# SCH.net
KiCad netlist of a schematic drawn in Altium Designer
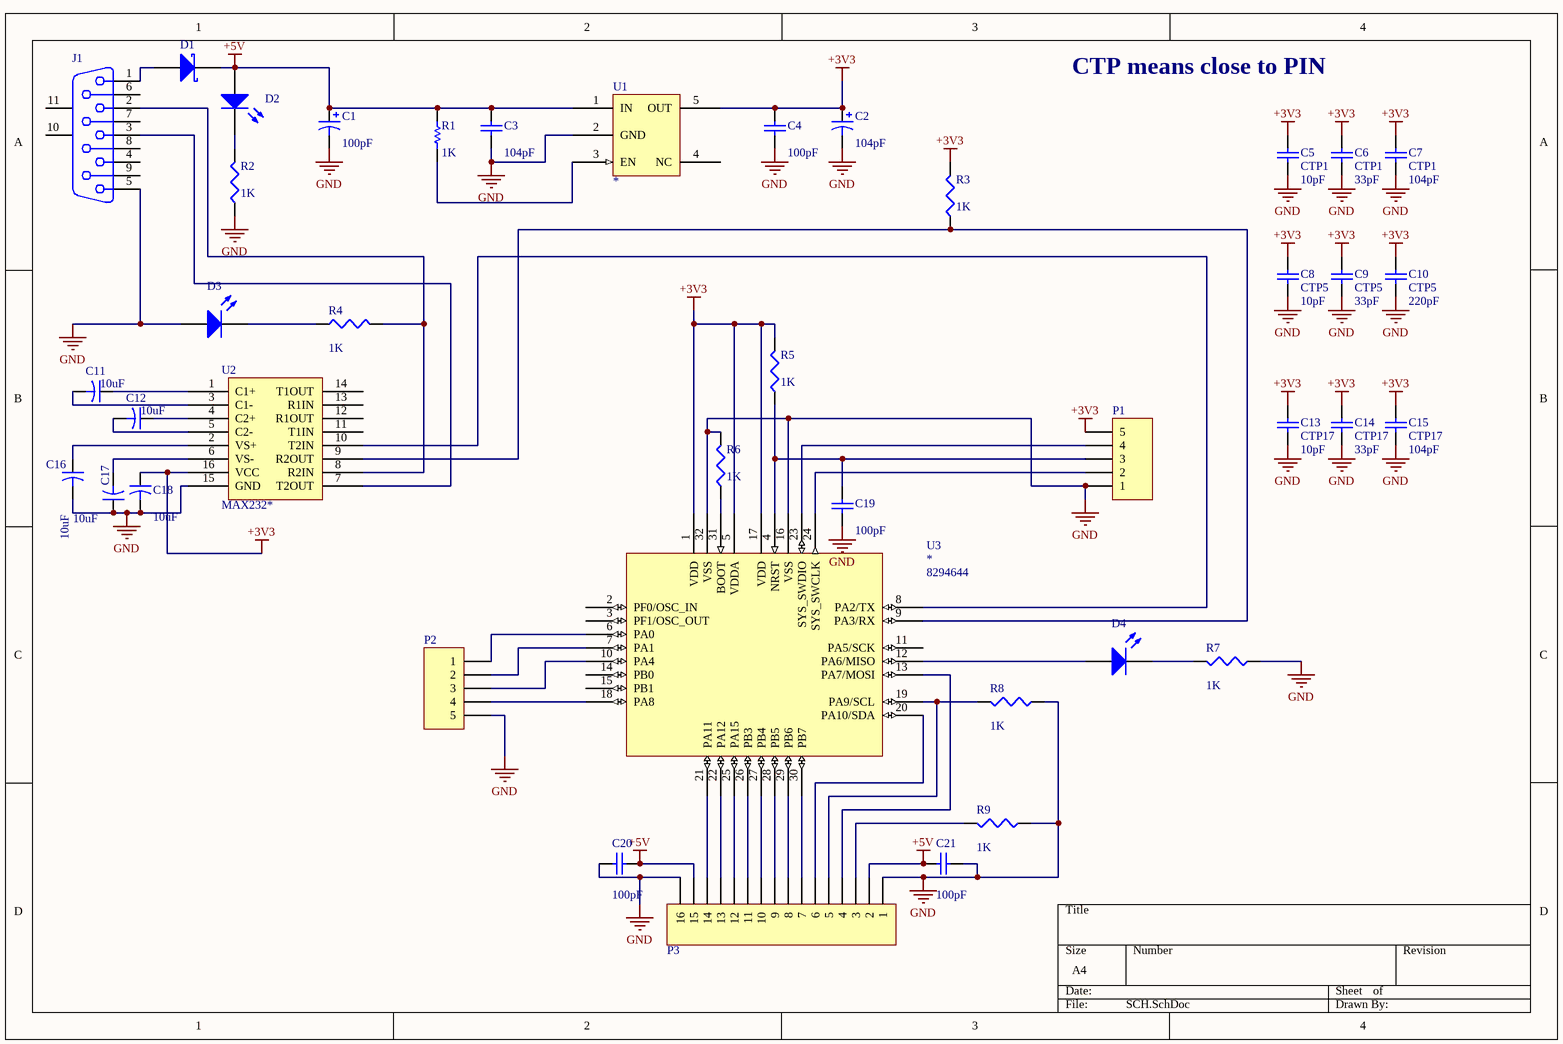
[diagram p0: SCH.SchDoc]

(export (version "E")
  (design (tool "Eeschema 10.0.6"))
  (components
    (comp (ref "C1")
      (value "100pF")
      (footprint "RB7.6-15")
      (description "Polarized Capacitor (Radial)")
      (fields (field (name "PUBLISHER") "Altium Limited"))
      (libsource (lib "Miscellaneous Devices") (part "Cap Pol1"))
    )
    (comp (ref "C2")
      (value "104pF")
      (footprint "RB7.6-15")
      (description "Polarized Capacitor (Radial)")
      (fields (field (name "PUBLISHER") "Altium Limited"))
      (libsource (lib "Miscellaneous Devices") (part "Cap Pol1"))
    )
    (comp (ref "C3")
      (value "104pF")
      (footprint "0603")
      (description "Capacitor")
      (fields (field (name "PUBLISHER") "Altium Limited"))
      (libsource (lib "Miscellaneous Devices") (part "Cap"))
    )
    (comp (ref "C4")
      (value "100pF")
      (footprint "0603")
      (description "Capacitor")
      (fields (field (name "PUBLISHER") "Altium Limited"))
      (libsource (lib "Miscellaneous Devices") (part "Cap"))
    )
    (comp (ref "C5")
      (value "CTP1")
      (footprint "0603")
      (description "Capacitor")
      (fields (field (name "ALTIUM_VALUE") "10pF") (field (name "PUBLISHER") "Altium Limited"))
      (libsource (lib "Miscellaneous Devices") (part "Cap"))
    )
    (comp (ref "C6")
      (value "CTP1")
      (footprint "0603")
      (description "Capacitor")
      (fields (field (name "ALTIUM_VALUE") "33pF") (field (name "PUBLISHER") "Altium Limited"))
      (libsource (lib "Miscellaneous Devices") (part "Cap"))
    )
    (comp (ref "C7")
      (value "CTP1")
      (footprint "0603")
      (description "Capacitor")
      (fields (field (name "ALTIUM_VALUE") "104pF") (field (name "PUBLISHER") "Altium Limited"))
      (libsource (lib "Miscellaneous Devices") (part "Cap"))
    )
    (comp (ref "C8")
      (value "CTP5")
      (footprint "0603")
      (description "Capacitor")
      (fields (field (name "ALTIUM_VALUE") "10pF") (field (name "PUBLISHER") "Altium Limited"))
      (libsource (lib "Miscellaneous Devices") (part "Cap"))
    )
    (comp (ref "C9")
      (value "CTP5")
      (footprint "0603")
      (description "Capacitor")
      (fields (field (name "ALTIUM_VALUE") "33pF") (field (name "PUBLISHER") "Altium Limited"))
      (libsource (lib "Miscellaneous Devices") (part "Cap"))
    )
    (comp (ref "C10")
      (value "CTP5")
      (footprint "0603")
      (description "Capacitor")
      (fields (field (name "ALTIUM_VALUE") "220pF") (field (name "PUBLISHER") "Altium Limited"))
      (libsource (lib "Miscellaneous Devices") (part "Cap"))
    )
    (comp (ref "C11")
      (value "10uF")
      (footprint "CAPR5-4X5")
      (description "Capacitor")
      (fields (field (name "PUBLISHER") "Altium Limited"))
      (libsource (lib "Miscellaneous Devices") (part "Cap2"))
    )
    (comp (ref "C12")
      (value "10uF")
      (footprint "CAPR5-4X5")
      (description "Capacitor")
      (fields (field (name "PUBLISHER") "Altium Limited"))
      (libsource (lib "Miscellaneous Devices") (part "Cap2"))
    )
    (comp (ref "C13")
      (value "CTP17")
      (footprint "0603")
      (description "Capacitor")
      (fields (field (name "ALTIUM_VALUE") "10pF") (field (name "PUBLISHER") "Altium Limited"))
      (libsource (lib "Miscellaneous Devices") (part "Cap"))
    )
    (comp (ref "C14")
      (value "CTP17")
      (footprint "0603")
      (description "Capacitor")
      (fields (field (name "ALTIUM_VALUE") "33pF") (field (name "PUBLISHER") "Altium Limited"))
      (libsource (lib "Miscellaneous Devices") (part "Cap"))
    )
    (comp (ref "C15")
      (value "CTP17")
      (footprint "0603")
      (description "Capacitor")
      (fields (field (name "ALTIUM_VALUE") "104pF") (field (name "PUBLISHER") "Altium Limited"))
      (libsource (lib "Miscellaneous Devices") (part "Cap"))
    )
    (comp (ref "C16")
      (value "10uF")
      (footprint "CAPR5-4X5")
      (description "Capacitor")
      (fields (field (name "PUBLISHER") "Altium Limited"))
      (libsource (lib "Miscellaneous Devices") (part "Cap2"))
    )
    (comp (ref "C17")
      (value "10uF")
      (footprint "CAPR5-4X5")
      (description "Capacitor")
      (fields (field (name "PUBLISHER") "Altium Limited"))
      (libsource (lib "Miscellaneous Devices") (part "Cap2"))
    )
    (comp (ref "C18")
      (value "10uF")
      (footprint "CAPR5-4X5")
      (description "Capacitor")
      (fields (field (name "PUBLISHER") "Altium Limited"))
      (libsource (lib "Miscellaneous Devices") (part "Cap2"))
    )
    (comp (ref "C19")
      (value "100pF")
      (footprint "0603")
      (description "Capacitor")
      (fields (field (name "PUBLISHER") "Altium Limited"))
      (libsource (lib "Miscellaneous Devices") (part "Cap"))
    )
    (comp (ref "C20")
      (value "100pF")
      (footprint "0603")
      (description "Capacitor")
      (fields (field (name "PUBLISHER") "Altium Limited"))
      (libsource (lib "Miscellaneous Devices") (part "Cap"))
    )
    (comp (ref "C21")
      (value "100pF")
      (footprint "0603")
      (description "Capacitor")
      (fields (field (name "PUBLISHER") "Altium Limited"))
      (libsource (lib "Miscellaneous Devices") (part "Cap"))
    )
    (comp (ref "D1")
      (value "~")
      (footprint "SMB")
      (description "Schottky Diode")
      (fields (field (name "PUBLISHER") "Altium Limited"))
      (libsource (lib "Miscellaneous Devices") (part "D Schottky"))
    )
    (comp (ref "D2")
      (value "~")
      (footprint "0805D")
      (description "Typical INFRARED GaAs LED")
      (fields (field (name "PUBLISHER") "Altium Limited"))
      (libsource (lib "Miscellaneous Devices") (part "LED0"))
    )
    (comp (ref "D3")
      (value "~")
      (footprint "0805D")
      (description "Typical INFRARED GaAs LED")
      (fields (field (name "PUBLISHER") "Altium Limited"))
      (libsource (lib "Miscellaneous Devices") (part "LED0"))
    )
    (comp (ref "D4")
      (value "~")
      (footprint "0805D")
      (description "Typical INFRARED GaAs LED")
      (fields (field (name "PUBLISHER") "Altium Limited"))
      (libsource (lib "Miscellaneous Devices") (part "LED0"))
    )
    (comp (ref "J1")
      (value "~")
      (footprint "DSUB1.385-2H9")
      (description "Receptacle Assembly, 9 Position, Right Angle")
      (fields (field (name "PUBLISHER") "Altium Limited"))
      (libsource (lib "Miscellaneous Connectors") (part "D Connector 9"))
    )
    (comp (ref "P1")
      (value "~")
      (footprint "HDR1X5")
      (description "Header, 5-Pin")
      (fields (field (name "PUBLISHER") "Altium Limited"))
      (libsource (lib "") (part "Header 5_1"))
    )
    (comp (ref "P2")
      (value "~")
      (footprint "HDR1X5")
      (description "Header, 5-Pin")
      (fields (field (name "PUBLISHER") "Altium Limited"))
      (libsource (lib "Miscellaneous Connectors") (part "Header 5"))
    )
    (comp (ref "P3")
      (value "~")
      (footprint "HDR1X16")
      (description "Header, 16-Pin")
      (fields (field (name "PUBLISHER") "Altium Limited"))
      (libsource (lib "Miscellaneous Connectors") (part "Header 16"))
    )
    (comp (ref "R1")
      (value "1K")
      (footprint "0603")
      (description "Semiconductor Resistor")
      (fields (field (name "PUBLISHER") "Altium Limited"))
      (libsource (lib "Miscellaneous Devices") (part "Res Semi"))
    )
    (comp (ref "R2")
      (value "1K")
      (footprint "0603")
      (description "Resistor")
      (fields (field (name "PUBLISHER") "Altium Limited"))
      (libsource (lib "Miscellaneous Devices") (part "Res3"))
    )
    (comp (ref "R3")
      (value "1K")
      (footprint "0603")
      (description "Resistor")
      (fields (field (name "PUBLISHER") "Altium Limited"))
      (libsource (lib "Miscellaneous Devices") (part "Res3"))
    )
    (comp (ref "R4")
      (value "1K")
      (footprint "0603")
      (description "Resistor")
      (fields (field (name "PUBLISHER") "Altium Limited"))
      (libsource (lib "Miscellaneous Devices") (part "Res3"))
    )
    (comp (ref "R5")
      (value "1K")
      (footprint "0603")
      (description "Resistor")
      (fields (field (name "PUBLISHER") "Altium Limited"))
      (libsource (lib "Miscellaneous Devices") (part "Res3"))
    )
    (comp (ref "R6")
      (value "1K")
      (footprint "0603")
      (description "Resistor")
      (fields (field (name "PUBLISHER") "Altium Limited"))
      (libsource (lib "") (part "Res3_1"))
    )
    (comp (ref "R7")
      (value "1K")
      (footprint "0603")
      (description "Resistor")
      (fields (field (name "PUBLISHER") "Altium Limited"))
      (libsource (lib "") (part "Res3_1"))
    )
    (comp (ref "R8")
      (value "1K")
      (footprint "0603")
      (description "Resistor")
      (fields (field (name "PUBLISHER") "Altium Limited"))
      (libsource (lib "") (part "Res3_1"))
    )
    (comp (ref "R9")
      (value "1K")
      (footprint "0603")
      (description "Resistor")
      (fields (field (name "PUBLISHER") "Altium Limited"))
      (libsource (lib "") (part "Res3_1"))
    )
    (comp (ref "U1") (value "*") (footprint "SOT-23-5L") (libsource (lib "MyAltiumSchlib1") (part "VRH3302")))
    (comp (ref "U2")
      (value "MAX232*")
      (footprint "SSOP16")
      (libsource (lib "MyAltiumSchlib1") (part "MAX232"))
    )
    (comp (ref "U3")
      (value "*")
      (footprint "LQFP32")
      (fields (field (name "SUPPLIER PART NUMBER 1") "8294644"))
      (libsource (lib "MyAltiumSchlib1") (part "STM32F030K6"))
    )
  )
  (nets
    (net (code "1") (name "+3V3") (class "Default")
      (node (ref "C10") (pin "2") (pinfunction "2_2") (pintype "passive"))
      (node (ref "C13") (pin "2") (pinfunction "2_2") (pintype "passive"))
      (node (ref "C14") (pin "2") (pinfunction "2_2") (pintype "passive"))
      (node (ref "C15") (pin "2") (pinfunction "2_2") (pintype "passive"))
      (node (ref "C18") (pin "1") (pinfunction "1_1") (pintype "passive"))
      (node (ref "C2") (pin "1") (pinfunction "1_1") (pintype "passive"))
      (node (ref "C4") (pin "2") (pinfunction "2_2") (pintype "passive"))
      (node (ref "C5") (pin "2") (pinfunction "2_2") (pintype "passive"))
      (node (ref "C6") (pin "2") (pinfunction "2_2") (pintype "passive"))
      (node (ref "C7") (pin "2") (pinfunction "2_2") (pintype "passive"))
      (node (ref "C8") (pin "2") (pinfunction "2_2") (pintype "passive"))
      (node (ref "C9") (pin "2") (pinfunction "2_2") (pintype "passive"))
      (node (ref "P1") (pin "5") (pinfunction "5_5") (pintype "passive"))
      (node (ref "R3") (pin "2") (pinfunction "2_2") (pintype "passive"))
      (node (ref "R5") (pin "2") (pinfunction "2_2") (pintype "passive"))
      (node (ref "U1") (pin "5") (pinfunction "OUT_5") (pintype "power_in"))
      (node (ref "U2") (pin "16") (pinfunction "VCC_16") (pintype "passive"))
      (node (ref "U3") (pin "1") (pinfunction "VDD_1") (pintype "power_in"))
      (node (ref "U3") (pin "17") (pinfunction "VDD_17") (pintype "power_in"))
      (node (ref "U3") (pin "5") (pinfunction "VDDA_5") (pintype "power_in"))
    )
    (net (code "2") (name "+5V") (class "Default")
      (node (ref "C1") (pin "1") (pinfunction "1_1") (pintype "passive"))
      (node (ref "C20") (pin "1") (pinfunction "1_1") (pintype "passive"))
      (node (ref "C21") (pin "2") (pinfunction "2_2") (pintype "passive"))
      (node (ref "C3") (pin "2") (pinfunction "2_2") (pintype "passive"))
      (node (ref "D1") (pin "2") (pinfunction "K_2") (pintype "passive"))
      (node (ref "D2") (pin "1") (pinfunction "A_1") (pintype "passive"))
      (node (ref "P3") (pin "15") (pinfunction "15_15") (pintype "passive"))
      (node (ref "P3") (pin "2") (pinfunction "2_2") (pintype "passive"))
      (node (ref "R1") (pin "2") (pinfunction "2_2") (pintype "passive"))
      (node (ref "U1") (pin "1") (pinfunction "IN_1") (pintype "power_in"))
    )
    (net (code "3") (name "GND") (class "Default")
      (node (ref "C1") (pin "2") (pinfunction "2_2") (pintype "passive"))
      (node (ref "C10") (pin "1") (pinfunction "1_1") (pintype "passive"))
      (node (ref "C13") (pin "1") (pinfunction "1_1") (pintype "passive"))
      (node (ref "C14") (pin "1") (pinfunction "1_1") (pintype "passive"))
      (node (ref "C15") (pin "1") (pinfunction "1_1") (pintype "passive"))
      (node (ref "C16") (pin "2") (pinfunction "2_2") (pintype "passive"))
      (node (ref "C17") (pin "1") (pinfunction "1_1") (pintype "passive"))
      (node (ref "C18") (pin "2") (pinfunction "2_2") (pintype "passive"))
      (node (ref "C19") (pin "1") (pinfunction "1_1") (pintype "passive"))
      (node (ref "C2") (pin "2") (pinfunction "2_2") (pintype "passive"))
      (node (ref "C20") (pin "2") (pinfunction "2_2") (pintype "passive"))
      (node (ref "C21") (pin "1") (pinfunction "1_1") (pintype "passive"))
      (node (ref "C3") (pin "1") (pinfunction "1_1") (pintype "passive"))
      (node (ref "C4") (pin "1") (pinfunction "1_1") (pintype "passive"))
      (node (ref "C5") (pin "1") (pinfunction "1_1") (pintype "passive"))
      (node (ref "C6") (pin "1") (pinfunction "1_1") (pintype "passive"))
      (node (ref "C7") (pin "1") (pinfunction "1_1") (pintype "passive"))
      (node (ref "C8") (pin "1") (pinfunction "1_1") (pintype "passive"))
      (node (ref "C9") (pin "1") (pinfunction "1_1") (pintype "passive"))
      (node (ref "D3") (pin "1") (pinfunction "A_1") (pintype "passive"))
      (node (ref "J1") (pin "5") (pinfunction "5_5") (pintype "passive"))
      (node (ref "P1") (pin "1") (pinfunction "1_1") (pintype "passive"))
      (node (ref "P2") (pin "5") (pinfunction "5_5") (pintype "passive"))
      (node (ref "P3") (pin "1") (pinfunction "1_1") (pintype "passive"))
      (node (ref "P3") (pin "16") (pinfunction "16_16") (pintype "passive"))
      (node (ref "R2") (pin "1") (pinfunction "1_1") (pintype "passive"))
      (node (ref "R6") (pin "1") (pinfunction "1_1") (pintype "passive"))
      (node (ref "R7") (pin "2") (pinfunction "2_2") (pintype "passive"))
      (node (ref "R8") (pin "2") (pinfunction "2_2") (pintype "passive"))
      (node (ref "R9") (pin "2") (pinfunction "2_2") (pintype "passive"))
      (node (ref "U1") (pin "2") (pinfunction "GND_2") (pintype "power_in"))
      (node (ref "U2") (pin "15") (pinfunction "GND_15") (pintype "passive"))
      (node (ref "U3") (pin "16") (pinfunction "VSS_16") (pintype "power_in"))
      (node (ref "U3") (pin "32") (pinfunction "VSS_32") (pintype "power_in"))
    )
    (net (code "4") (name "Net-(D1-A)") (class "Default")
      (node (ref "D1") (pin "1") (pinfunction "A_1") (pintype "passive"))
      (node (ref "J1") (pin "1") (pinfunction "1_1") (pintype "passive"))
    )
    (net (code "5") (name "Net-(D2-K)") (class "Default")
      (node (ref "D2") (pin "2") (pinfunction "K_2") (pintype "passive"))
      (node (ref "R2") (pin "2") (pinfunction "2_2") (pintype "passive"))
    )
    (net (code "6") (name "Net-(D3-K)") (class "Default")
      (node (ref "D3") (pin "2") (pinfunction "K_2") (pintype "passive"))
      (node (ref "R4") (pin "1") (pinfunction "1_1") (pintype "passive"))
    )
    (net (code "7") (name "Net-(D4-A)") (class "Default")
      (node (ref "D4") (pin "1") (pinfunction "A_1") (pintype "passive"))
      (node (ref "U3") (pin "12") (pinfunction "PA6/MISO_12") (pintype "bidirectional"))
    )
    (net (code "8") (name "Net-(D4-K)") (class "Default")
      (node (ref "D4") (pin "2") (pinfunction "K_2") (pintype "passive"))
      (node (ref "R7") (pin "1") (pinfunction "1_1") (pintype "passive"))
    )
    (net (code "9") (name "Net-(P3-Pad3)") (class "Default")
      (node (ref "P3") (pin "3") (pinfunction "3_3") (pintype "passive"))
      (node (ref "R9") (pin "1") (pinfunction "1_1") (pintype "passive"))
    )
    (net (code "10") (name "Net-(U1-EN)") (class "Default")
      (node (ref "R1") (pin "1") (pinfunction "1_1") (pintype "passive"))
      (node (ref "U1") (pin "3") (pinfunction "EN_3") (pintype "input"))
    )
    (net (code "11") (name "Net-(U2-C1+)") (class "Default")
      (node (ref "C11") (pin "1") (pinfunction "1_1") (pintype "passive"))
      (node (ref "U2") (pin "1") (pinfunction "C1+_1") (pintype "passive"))
    )
    (net (code "12") (name "Net-(U2-C1-)") (class "Default")
      (node (ref "C11") (pin "2") (pinfunction "2_2") (pintype "passive"))
      (node (ref "U2") (pin "3") (pinfunction "C1-_3") (pintype "passive"))
    )
    (net (code "13") (name "Net-(U2-C2+)") (class "Default")
      (node (ref "C12") (pin "1") (pinfunction "1_1") (pintype "passive"))
      (node (ref "U2") (pin "4") (pinfunction "C2+_4") (pintype "passive"))
    )
    (net (code "14") (name "Net-(U2-C2-)") (class "Default")
      (node (ref "C12") (pin "2") (pinfunction "2_2") (pintype "passive"))
      (node (ref "U2") (pin "5") (pinfunction "C2-_5") (pintype "passive"))
    )
    (net (code "15") (name "Net-(U2-R2IN)") (class "Default")
      (node (ref "J1") (pin "2") (pinfunction "2_2") (pintype "passive"))
      (node (ref "R4") (pin "2") (pinfunction "2_2") (pintype "passive"))
      (node (ref "U2") (pin "8") (pinfunction "R2IN_8") (pintype "passive"))
    )
    (net (code "16") (name "Net-(U2-R2OUT)") (class "Default")
      (node (ref "R3") (pin "1") (pinfunction "1_1") (pintype "passive"))
      (node (ref "U2") (pin "9") (pinfunction "R2OUT_9") (pintype "passive"))
      (node (ref "U3") (pin "9") (pinfunction "PA3/RX_9") (pintype "bidirectional"))
    )
    (net (code "17") (name "Net-(U2-T2IN)") (class "Default")
      (node (ref "U2") (pin "10") (pinfunction "T2IN_10") (pintype "passive"))
      (node (ref "U3") (pin "8") (pinfunction "PA2/TX_8") (pintype "bidirectional"))
    )
    (net (code "18") (name "Net-(U2-T2OUT)") (class "Default")
      (node (ref "J1") (pin "3") (pinfunction "3_3") (pintype "passive"))
      (node (ref "U2") (pin "7") (pinfunction "T2OUT_7") (pintype "passive"))
    )
    (net (code "19") (name "Net-(U2-VS+)") (class "Default")
      (node (ref "C16") (pin "1") (pinfunction "1_1") (pintype "passive"))
      (node (ref "U2") (pin "2") (pinfunction "VS+_2") (pintype "passive"))
    )
    (net (code "20") (name "Net-(U2-VS-)") (class "Default")
      (node (ref "C17") (pin "2") (pinfunction "2_2") (pintype "passive"))
      (node (ref "U2") (pin "6") (pinfunction "VS-_6") (pintype "passive"))
    )
    (net (code "21") (name "Net-(U3-BOOT)") (class "Default")
      (node (ref "R6") (pin "2") (pinfunction "2_2") (pintype "passive"))
      (node (ref "U3") (pin "31") (pinfunction "BOOT_31") (pintype "input"))
    )
    (net (code "22") (name "Net-(U3-NRST)") (class "Default")
      (node (ref "C19") (pin "2") (pinfunction "2_2") (pintype "passive"))
      (node (ref "P1") (pin "3") (pinfunction "3_3") (pintype "passive"))
      (node (ref "R5") (pin "1") (pinfunction "1_1") (pintype "passive"))
      (node (ref "U3") (pin "4") (pinfunction "NRST_4") (pintype "input"))
    )
    (net (code "23") (name "Net-(U3-PA0)") (class "Default")
      (node (ref "P2") (pin "1") (pinfunction "1_1") (pintype "passive"))
      (node (ref "U3") (pin "6") (pinfunction "PA0_6") (pintype "bidirectional"))
    )
    (net (code "24") (name "Net-(U3-PA1)") (class "Default")
      (node (ref "P2") (pin "2") (pinfunction "2_2") (pintype "passive"))
      (node (ref "U3") (pin "7") (pinfunction "PA1_7") (pintype "bidirectional"))
    )
    (net (code "25") (name "Net-(U3-PA4)") (class "Default")
      (node (ref "P2") (pin "3") (pinfunction "3_3") (pintype "passive"))
      (node (ref "U3") (pin "10") (pinfunction "PA4_10") (pintype "bidirectional"))
    )
    (net (code "26") (name "Net-(U3-PA7{slash}MOSI)") (class "Default")
      (node (ref "P3") (pin "4") (pinfunction "4_4") (pintype "passive"))
      (node (ref "U3") (pin "13") (pinfunction "PA7/MOSI_13") (pintype "bidirectional"))
    )
    (net (code "27") (name "Net-(U3-PA8)") (class "Default")
      (node (ref "P2") (pin "4") (pinfunction "4_4") (pintype "passive"))
      (node (ref "U3") (pin "18") (pinfunction "PA8_18") (pintype "bidirectional"))
    )
    (net (code "28") (name "Net-(U3-PA9{slash}SCL)") (class "Default")
      (node (ref "P3") (pin "5") (pinfunction "5_5") (pintype "passive"))
      (node (ref "R8") (pin "1") (pinfunction "1_1") (pintype "passive"))
      (node (ref "U3") (pin "19") (pinfunction "PA9/SCL_19") (pintype "bidirectional"))
    )
    (net (code "29") (name "Net-(U3-PA10{slash}SDA)") (class "Default")
      (node (ref "P3") (pin "6") (pinfunction "6_6") (pintype "passive"))
      (node (ref "U3") (pin "20") (pinfunction "PA10/SDA_20") (pintype "bidirectional"))
    )
    (net (code "30") (name "Net-(U3-PA11)") (class "Default")
      (node (ref "P3") (pin "14") (pinfunction "14_14") (pintype "passive"))
      (node (ref "U3") (pin "21") (pinfunction "PA11_21") (pintype "bidirectional"))
    )
    (net (code "31") (name "Net-(U3-PA12)") (class "Default")
      (node (ref "P3") (pin "13") (pinfunction "13_13") (pintype "passive"))
      (node (ref "U3") (pin "22") (pinfunction "PA12_22") (pintype "bidirectional"))
    )
    (net (code "32") (name "Net-(U3-PA15)") (class "Default")
      (node (ref "P3") (pin "12") (pinfunction "12_12") (pintype "passive"))
      (node (ref "U3") (pin "25") (pinfunction "PA15_25") (pintype "bidirectional"))
    )
    (net (code "33") (name "Net-(U3-PB3)") (class "Default")
      (node (ref "P3") (pin "11") (pinfunction "11_11") (pintype "passive"))
      (node (ref "U3") (pin "26") (pinfunction "PB3_26") (pintype "bidirectional"))
    )
    (net (code "34") (name "Net-(U3-PB4)") (class "Default")
      (node (ref "P3") (pin "10") (pinfunction "10_10") (pintype "passive"))
      (node (ref "U3") (pin "27") (pinfunction "PB4_27") (pintype "bidirectional"))
    )
    (net (code "35") (name "Net-(U3-PB5)") (class "Default")
      (node (ref "P3") (pin "9") (pinfunction "9_9") (pintype "passive"))
      (node (ref "U3") (pin "28") (pinfunction "PB5_28") (pintype "bidirectional"))
    )
    (net (code "36") (name "Net-(U3-PB6)") (class "Default")
      (node (ref "P3") (pin "8") (pinfunction "8_8") (pintype "passive"))
      (node (ref "U3") (pin "29") (pinfunction "PB6_29") (pintype "bidirectional"))
    )
    (net (code "37") (name "Net-(U3-PB7)") (class "Default")
      (node (ref "P3") (pin "7") (pinfunction "7_7") (pintype "passive"))
      (node (ref "U3") (pin "30") (pinfunction "PB7_30") (pintype "bidirectional"))
    )
    (net (code "38") (name "Net-(U3-SYS_SWCLK)") (class "Default")
      (node (ref "P1") (pin "2") (pinfunction "2_2") (pintype "passive"))
      (node (ref "U3") (pin "24") (pinfunction "SYS_SWCLK_24") (pintype "output"))
    )
    (net (code "39") (name "Net-(U3-SYS_SWDIO)") (class "Default")
      (node (ref "P1") (pin "4") (pinfunction "4_4") (pintype "passive"))
      (node (ref "U3") (pin "23") (pinfunction "SYS_SWDIO_23") (pintype "bidirectional"))
    )
    (net (code "40") (name "unconnected-(J1-MH1-Pad10)") (class "Default")
      (node (ref "J1") (pin "10") (pinfunction "MH1_10") (pintype "passive"))
    )
    (net (code "41") (name "unconnected-(J1-MH2-Pad11)") (class "Default")
      (node (ref "J1") (pin "11") (pinfunction "MH2_11") (pintype "passive"))
    )
    (net (code "42") (name "unconnected-(J1-Pad4)") (class "Default")
      (node (ref "J1") (pin "4") (pinfunction "4_4") (pintype "passive"))
    )
    (net (code "43") (name "unconnected-(J1-Pad6)") (class "Default")
      (node (ref "J1") (pin "6") (pinfunction "6_6") (pintype "passive"))
    )
    (net (code "44") (name "unconnected-(J1-Pad7)") (class "Default")
      (node (ref "J1") (pin "7") (pinfunction "7_7") (pintype "passive"))
    )
    (net (code "45") (name "unconnected-(J1-Pad8)") (class "Default")
      (node (ref "J1") (pin "8") (pinfunction "8_8") (pintype "passive"))
    )
    (net (code "46") (name "unconnected-(J1-Pad9)") (class "Default")
      (node (ref "J1") (pin "9") (pinfunction "9_9") (pintype "passive"))
    )
    (net (code "47") (name "unconnected-(U1-NC-Pad4)") (class "Default")
      (node (ref "U1") (pin "4") (pinfunction "NC_4") (pintype "passive"))
    )
    (net (code "48") (name "unconnected-(U2-R1IN-Pad13)") (class "Default")
      (node (ref "U2") (pin "13") (pinfunction "R1IN_13") (pintype "passive"))
    )
    (net (code "49") (name "unconnected-(U2-R1OUT-Pad12)") (class "Default")
      (node (ref "U2") (pin "12") (pinfunction "R1OUT_12") (pintype "passive"))
    )
    (net (code "50") (name "unconnected-(U2-T1IN-Pad11)") (class "Default")
      (node (ref "U2") (pin "11") (pinfunction "T1IN_11") (pintype "passive"))
    )
    (net (code "51") (name "unconnected-(U2-T1OUT-Pad14)") (class "Default")
      (node (ref "U2") (pin "14") (pinfunction "T1OUT_14") (pintype "passive"))
    )
    (net (code "52") (name "unconnected-(U3-PA5{slash}SCK-Pad11)") (class "Default")
      (node (ref "U3") (pin "11") (pinfunction "PA5/SCK_11") (pintype "bidirectional"))
    )
    (net (code "53") (name "unconnected-(U3-PB0-Pad14)") (class "Default")
      (node (ref "U3") (pin "14") (pinfunction "PB0_14") (pintype "bidirectional"))
    )
    (net (code "54") (name "unconnected-(U3-PB1-Pad15)") (class "Default")
      (node (ref "U3") (pin "15") (pinfunction "PB1_15") (pintype "bidirectional"))
    )
    (net (code "55") (name "unconnected-(U3-PF0{slash}OSC_IN-Pad2)") (class "Default")
      (node (ref "U3") (pin "2") (pinfunction "PF0/OSC_IN_2") (pintype "bidirectional"))
    )
    (net (code "56") (name "unconnected-(U3-PF1{slash}OSC_OUT-Pad3)") (class "Default")
      (node (ref "U3") (pin "3") (pinfunction "PF1/OSC_OUT_3") (pintype "bidirectional"))
    )
  )
)
